# --XXXX--.net
KiCad netlist of a schematic drawn in EAGLE
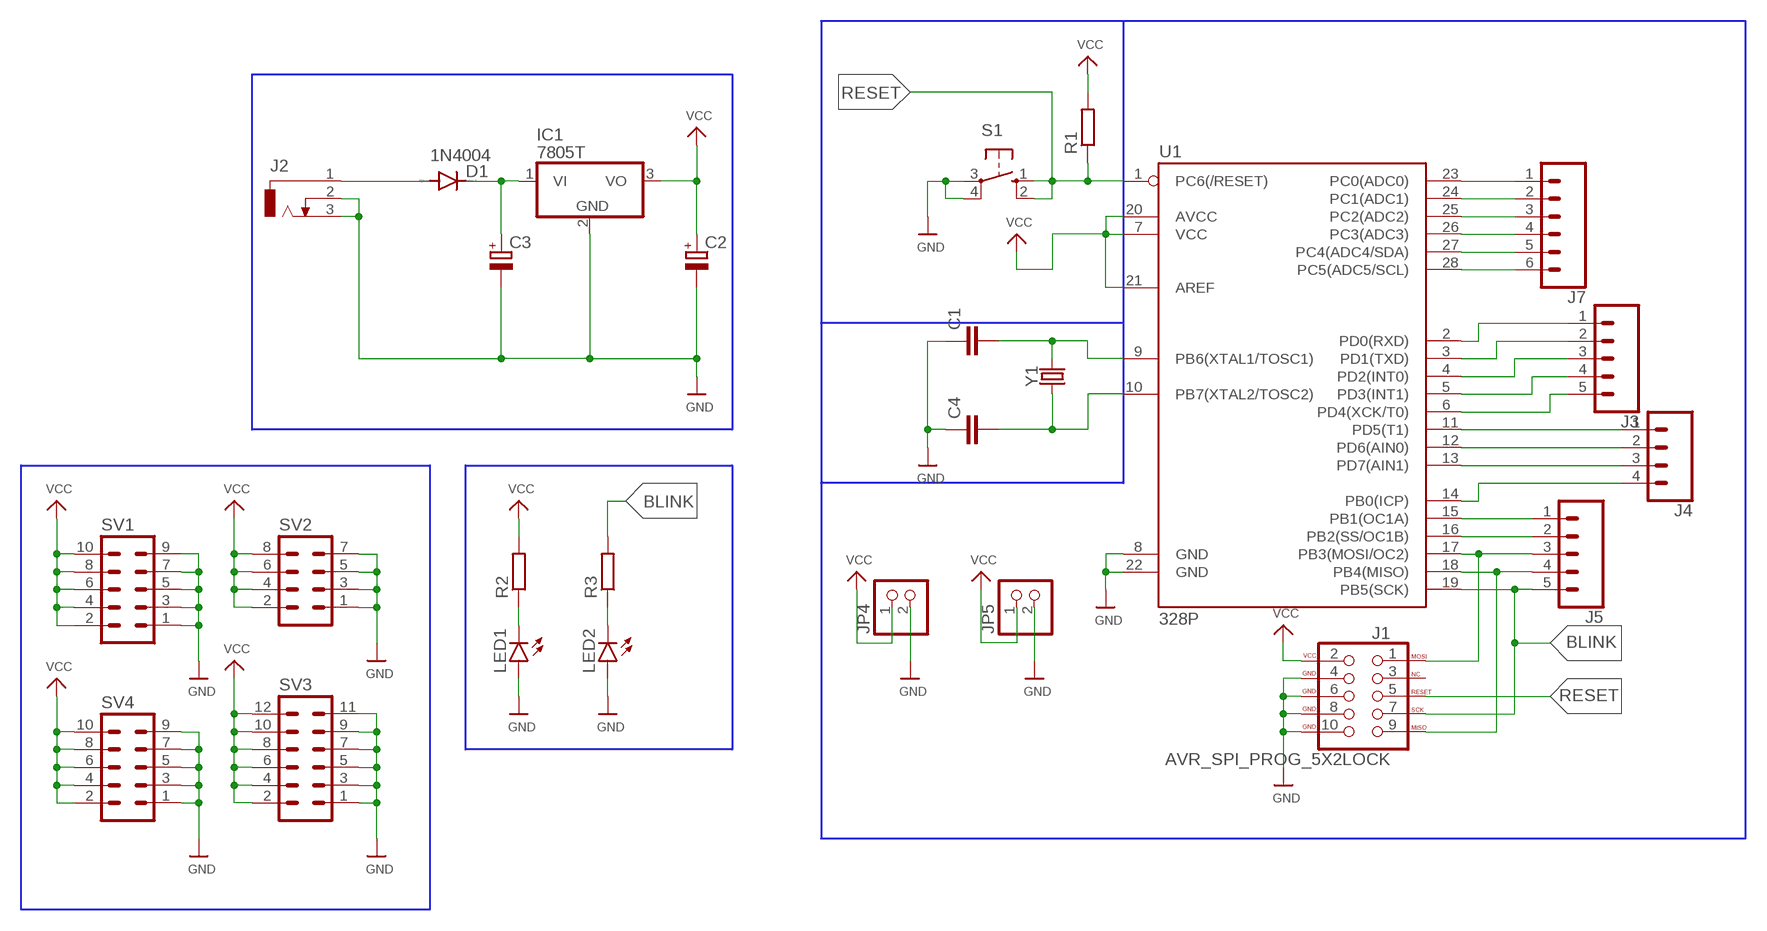
[diagram p0: schematic, sheet 1]

(export (version "E")
  (design (tool "Eeschema 10.0.6"))
  (components
    (comp (ref "C1")
      (value "C-EU050-024X044")
      (footprint "eagle-import:C050-024X044")
      (libsource (lib "eagle-import") (part "C-EU050-024X044"))
    )
    (comp (ref "C2")
      (value "CPOL-EUE2.5-5")
      (footprint "eagle-import:E2,5-5")
      (libsource (lib "eagle-import") (part "CPOL-EUE2.5-5"))
    )
    (comp (ref "C3")
      (value "CPOL-EUE2.5-7")
      (footprint "eagle-import:E2,5-7")
      (libsource (lib "eagle-import") (part "CPOL-EUE2.5-7"))
    )
    (comp (ref "C4")
      (value "C-EU050-024X044")
      (footprint "eagle-import:C050-024X044")
      (libsource (lib "eagle-import") (part "C-EU050-024X044"))
    )
    (comp (ref "D1")
      (value "1N4004")
      (footprint "eagle-import:DO41-10")
      (libsource (lib "eagle-import") (part "1N4004"))
    )
    (comp (ref "IC1")
      (value "7805T")
      (footprint "eagle-import:TO220H")
      (libsource (lib "eagle-import") (part "78T05"))
    )
    (comp (ref "J1")
      (value "AVR_SPI_PROG_5X2LOCK")
      (footprint "eagle-import:2X5-SHROUDED_LOCK")
      (libsource (lib "eagle-import") (part "AVR_SPI_PROG_5X2LOCK"))
    )
    (comp (ref "J2")
      (value "DCJ0303")
      (footprint "eagle-import:DCJ0303")
      (libsource (lib "eagle-import") (part "DCJ0303"))
    )
    (comp (ref "J3")
      (value "CONN_05")
      (footprint "eagle-import:1X05")
      (libsource (lib "eagle-import") (part "CONN_05"))
    )
    (comp (ref "J4")
      (value "CONN_04")
      (footprint "eagle-import:1X04")
      (libsource (lib "eagle-import") (part "CONN_04"))
    )
    (comp (ref "J5")
      (value "CONN_05")
      (footprint "eagle-import:1X05")
      (libsource (lib "eagle-import") (part "CONN_05"))
    )
    (comp (ref "J7")
      (value "CONN_06SILK_FEMALE_PTH")
      (footprint "eagle-import:1X06")
      (libsource (lib "eagle-import") (part "CONN_06SILK_FEMALE_PTH"))
    )
    (comp (ref "JP4")
      (value "PINHD-1X2")
      (footprint "eagle-import:1X02")
      (libsource (lib "eagle-import") (part "PINHD-1X2"))
    )
    (comp (ref "JP5")
      (value "PINHD-1X2")
      (footprint "eagle-import:1X02")
      (libsource (lib "eagle-import") (part "PINHD-1X2"))
    )
    (comp (ref "LED1")
      (value "LED3MM")
      (footprint "eagle-import:LED3MM")
      (libsource (lib "eagle-import") (part "LED3MM"))
    )
    (comp (ref "LED2")
      (value "LED3MM")
      (footprint "eagle-import:LED3MM")
      (libsource (lib "eagle-import") (part "LED3MM"))
    )
    (comp (ref "R1")
      (value "R-EU_0207/10")
      (footprint "eagle-import:0207_10")
      (libsource (lib "eagle-import") (part "R-EU_0207/10"))
    )
    (comp (ref "R2")
      (value "R-EU_0207/10")
      (footprint "eagle-import:0207_10")
      (libsource (lib "eagle-import") (part "R-EU_0207/10"))
    )
    (comp (ref "R3")
      (value "R-EU_0207/10")
      (footprint "eagle-import:0207_10")
      (libsource (lib "eagle-import") (part "R-EU_0207/10"))
    )
    (comp (ref "S1")
      (value "10-XX")
      (footprint "eagle-import:B3F-10XX")
      (fields (field (name "MPN") "B3F-1000"))
      (libsource (lib "eagle-import") (part "10-XX"))
    )
    (comp (ref "SV1")
      (value "MA05-2")
      (footprint "eagle-import:MA05-2")
      (libsource (lib "eagle-import") (part "MA05-2"))
    )
    (comp (ref "SV2")
      (value "MA04-2")
      (footprint "eagle-import:MA04-2")
      (libsource (lib "eagle-import") (part "MA04-2"))
    )
    (comp (ref "SV3")
      (value "MA06-2")
      (footprint "eagle-import:MA06-2")
      (libsource (lib "eagle-import") (part "MA06-2"))
    )
    (comp (ref "SV4")
      (value "MA05-2")
      (footprint "eagle-import:MA05-2")
      (libsource (lib "eagle-import") (part "MA05-2"))
    )
    (comp (ref "U1")
      (value "328P")
      (footprint "eagle-import:DIP28")
      (libsource (lib "eagle-import") (part "ATMEGA328P_PDIP"))
    )
    (comp (ref "Y1")
      (value "CRYSTALPTH-HC49UV")
      (footprint "eagle-import:HC49U")
      (libsource (lib "eagle-import") (part "CRYSTALPTH-HC49UV"))
    )
  )
  (nets
    (net (code "1") (name "/BLINK") (class "Default")
      (node (ref "J1") (pin "7") (pinfunction "SCK_7") (pintype "passive"))
      (node (ref "J5") (pin "5") (pinfunction "5_5") (pintype "passive"))
      (node (ref "R3") (pin "2") (pinfunction "2_2") (pintype "passive"))
      (node (ref "U1") (pin "19") (pinfunction "PB5(SCK)_19") (pintype "bidirectional"))
    )
    (net (code "2") (name "/RESET") (class "Default")
      (node (ref "J1") (pin "5") (pinfunction "RESET_5") (pintype "passive"))
      (node (ref "R1") (pin "1") (pinfunction "1_1") (pintype "passive"))
      (node (ref "S1") (pin "1") (pinfunction "S_1") (pintype "passive"))
      (node (ref "S1") (pin "2") (pinfunction "S1_2") (pintype "passive"))
      (node (ref "U1") (pin "1") (pinfunction "PC6(/RESET)_1") (pintype "bidirectional"))
    )
    (net (code "3") (name "GND") (class "Default")
      (node (ref "C1") (pin "1") (pinfunction "1_1") (pintype "passive"))
      (node (ref "C2") (pin "-") (pinfunction "-_-") (pintype "passive"))
      (node (ref "C3") (pin "-") (pinfunction "-_-") (pintype "passive"))
      (node (ref "C4") (pin "1") (pinfunction "1_1") (pintype "passive"))
      (node (ref "IC1") (pin "2") (pinfunction "GND_2") (pintype "passive"))
      (node (ref "J1") (pin "10") (pinfunction "GND_10") (pintype "power_in"))
      (node (ref "J1") (pin "4") (pinfunction "GND_4") (pintype "power_in"))
      (node (ref "J1") (pin "6") (pinfunction "GND_6") (pintype "power_in"))
      (node (ref "J1") (pin "8") (pinfunction "GND_8") (pintype "power_in"))
      (node (ref "J2") (pin "2") (pinfunction "2_2") (pintype "passive"))
      (node (ref "J2") (pin "3") (pinfunction "3_3") (pintype "passive"))
      (node (ref "JP4") (pin "2") (pinfunction "2_2") (pintype "passive"))
      (node (ref "JP5") (pin "2") (pinfunction "2_2") (pintype "passive"))
      (node (ref "LED1") (pin "A") (pinfunction "A_A") (pintype "passive"))
      (node (ref "LED2") (pin "A") (pinfunction "A_A") (pintype "passive"))
      (node (ref "S1") (pin "3") (pinfunction "P_3") (pintype "passive"))
      (node (ref "S1") (pin "4") (pinfunction "P1_4") (pintype "passive"))
      (node (ref "SV1") (pin "1") (pinfunction "1_1") (pintype "passive"))
      (node (ref "SV1") (pin "3") (pinfunction "3_3") (pintype "passive"))
      (node (ref "SV1") (pin "5") (pinfunction "5_5") (pintype "passive"))
      (node (ref "SV1") (pin "7") (pinfunction "7_7") (pintype "passive"))
      (node (ref "SV1") (pin "9") (pinfunction "9_9") (pintype "passive"))
      (node (ref "SV2") (pin "1") (pinfunction "1_1") (pintype "passive"))
      (node (ref "SV2") (pin "3") (pinfunction "3_3") (pintype "passive"))
      (node (ref "SV2") (pin "5") (pinfunction "5_5") (pintype "passive"))
      (node (ref "SV2") (pin "7") (pinfunction "7_7") (pintype "passive"))
      (node (ref "SV3") (pin "1") (pinfunction "1_1") (pintype "passive"))
      (node (ref "SV3") (pin "11") (pinfunction "11_11") (pintype "passive"))
      (node (ref "SV3") (pin "3") (pinfunction "3_3") (pintype "passive"))
      (node (ref "SV3") (pin "5") (pinfunction "5_5") (pintype "passive"))
      (node (ref "SV3") (pin "7") (pinfunction "7_7") (pintype "passive"))
      (node (ref "SV3") (pin "9") (pinfunction "9_9") (pintype "passive"))
      (node (ref "SV4") (pin "1") (pinfunction "1_1") (pintype "passive"))
      (node (ref "SV4") (pin "3") (pinfunction "3_3") (pintype "passive"))
      (node (ref "SV4") (pin "5") (pinfunction "5_5") (pintype "passive"))
      (node (ref "SV4") (pin "7") (pinfunction "7_7") (pintype "passive"))
      (node (ref "SV4") (pin "9") (pinfunction "9_9") (pintype "passive"))
      (node (ref "U1") (pin "22") (pinfunction "GND_22") (pintype "bidirectional"))
      (node (ref "U1") (pin "8") (pinfunction "GND_8") (pintype "bidirectional"))
    )
    (net (code "4") (name "Net-(D1-PadA)") (class "Default")
      (node (ref "D1") (pin "A") (pinfunction "A_A") (pintype "passive"))
      (node (ref "J2") (pin "1") (pinfunction "1_1") (pintype "passive"))
    )
    (net (code "5") (name "Net-(IC1-VI)") (class "Default")
      (node (ref "C3") (pin "+") (pinfunction "+_+") (pintype "passive"))
      (node (ref "D1") (pin "C") (pinfunction "C_C") (pintype "passive"))
      (node (ref "IC1") (pin "1") (pinfunction "VI_1") (pintype "input"))
    )
    (net (code "6") (name "Net-(J1-MISO)") (class "Default")
      (node (ref "J1") (pin "9") (pinfunction "MISO_9") (pintype "passive"))
      (node (ref "J5") (pin "4") (pinfunction "4_4") (pintype "passive"))
      (node (ref "U1") (pin "18") (pinfunction "PB4(MISO)_18") (pintype "bidirectional"))
    )
    (net (code "7") (name "Net-(J1-MOSI)") (class "Default")
      (node (ref "J1") (pin "1") (pinfunction "MOSI_1") (pintype "passive"))
      (node (ref "J5") (pin "3") (pinfunction "3_3") (pintype "passive"))
      (node (ref "U1") (pin "17") (pinfunction "PB3(MOSI/OC2)_17") (pintype "bidirectional"))
    )
    (net (code "8") (name "Net-(LED1-C)") (class "Default")
      (node (ref "LED1") (pin "K") (pinfunction "C_K") (pintype "passive"))
      (node (ref "R2") (pin "1") (pinfunction "1_1") (pintype "passive"))
    )
    (net (code "9") (name "Net-(LED2-C)") (class "Default")
      (node (ref "LED2") (pin "K") (pinfunction "C_K") (pintype "passive"))
      (node (ref "R3") (pin "1") (pinfunction "1_1") (pintype "passive"))
    )
    (net (code "10") (name "Net-(U1-PB0(ICP))") (class "Default")
      (node (ref "J4") (pin "4") (pinfunction "4_4") (pintype "passive"))
      (node (ref "U1") (pin "14") (pinfunction "PB0(ICP)_14") (pintype "bidirectional"))
    )
    (net (code "11") (name "Net-(U1-PB1(OC1A))") (class "Default")
      (node (ref "J5") (pin "1") (pinfunction "1_1") (pintype "passive"))
      (node (ref "U1") (pin "15") (pinfunction "PB1(OC1A)_15") (pintype "bidirectional"))
    )
    (net (code "12") (name "Net-(U1-PB2(SS{slash}OC1B))") (class "Default")
      (node (ref "J5") (pin "2") (pinfunction "2_2") (pintype "passive"))
      (node (ref "U1") (pin "16") (pinfunction "PB2(SS/OC1B)_16") (pintype "bidirectional"))
    )
    (net (code "13") (name "Net-(U1-PB6(XTAL1{slash}TOSC1))") (class "Default")
      (node (ref "C1") (pin "2") (pinfunction "2_2") (pintype "passive"))
      (node (ref "U1") (pin "9") (pinfunction "PB6(XTAL1/TOSC1)_9") (pintype "bidirectional"))
      (node (ref "Y1") (pin "2") (pinfunction "2_2") (pintype "passive"))
    )
    (net (code "14") (name "Net-(U1-PB7(XTAL2{slash}TOSC2))") (class "Default")
      (node (ref "C4") (pin "2") (pinfunction "2_2") (pintype "passive"))
      (node (ref "U1") (pin "10") (pinfunction "PB7(XTAL2/TOSC2)_10") (pintype "bidirectional"))
      (node (ref "Y1") (pin "1") (pinfunction "1_1") (pintype "passive"))
    )
    (net (code "15") (name "Net-(U1-PC0(ADC0))") (class "Default")
      (node (ref "J7") (pin "1") (pinfunction "1_1") (pintype "passive"))
      (node (ref "U1") (pin "23") (pinfunction "PC0(ADC0)_23") (pintype "bidirectional"))
    )
    (net (code "16") (name "Net-(U1-PC1(ADC1))") (class "Default")
      (node (ref "J7") (pin "2") (pinfunction "2_2") (pintype "passive"))
      (node (ref "U1") (pin "24") (pinfunction "PC1(ADC1)_24") (pintype "bidirectional"))
    )
    (net (code "17") (name "Net-(U1-PC2(ADC2))") (class "Default")
      (node (ref "J7") (pin "3") (pinfunction "3_3") (pintype "passive"))
      (node (ref "U1") (pin "25") (pinfunction "PC2(ADC2)_25") (pintype "bidirectional"))
    )
    (net (code "18") (name "Net-(U1-PC3(ADC3))") (class "Default")
      (node (ref "J7") (pin "4") (pinfunction "4_4") (pintype "passive"))
      (node (ref "U1") (pin "26") (pinfunction "PC3(ADC3)_26") (pintype "bidirectional"))
    )
    (net (code "19") (name "Net-(U1-PC4(ADC4{slash}SDA))") (class "Default")
      (node (ref "J7") (pin "5") (pinfunction "5_5") (pintype "passive"))
      (node (ref "U1") (pin "27") (pinfunction "PC4(ADC4/SDA)_27") (pintype "bidirectional"))
    )
    (net (code "20") (name "Net-(U1-PC5(ADC5{slash}SCL))") (class "Default")
      (node (ref "J7") (pin "6") (pinfunction "6_6") (pintype "passive"))
      (node (ref "U1") (pin "28") (pinfunction "PC5(ADC5/SCL)_28") (pintype "bidirectional"))
    )
    (net (code "21") (name "Net-(U1-PD0(RXD))") (class "Default")
      (node (ref "J3") (pin "1") (pinfunction "1_1") (pintype "passive"))
      (node (ref "U1") (pin "2") (pinfunction "PD0(RXD)_2") (pintype "bidirectional"))
    )
    (net (code "22") (name "Net-(U1-PD1(TXD))") (class "Default")
      (node (ref "J3") (pin "2") (pinfunction "2_2") (pintype "passive"))
      (node (ref "U1") (pin "3") (pinfunction "PD1(TXD)_3") (pintype "bidirectional"))
    )
    (net (code "23") (name "Net-(U1-PD2(INT0))") (class "Default")
      (node (ref "J3") (pin "3") (pinfunction "3_3") (pintype "passive"))
      (node (ref "U1") (pin "4") (pinfunction "PD2(INT0)_4") (pintype "bidirectional"))
    )
    (net (code "24") (name "Net-(U1-PD3(INT1))") (class "Default")
      (node (ref "J3") (pin "4") (pinfunction "4_4") (pintype "passive"))
      (node (ref "U1") (pin "5") (pinfunction "PD3(INT1)_5") (pintype "bidirectional"))
    )
    (net (code "25") (name "Net-(U1-PD4(XCK{slash}T0))") (class "Default")
      (node (ref "J3") (pin "5") (pinfunction "5_5") (pintype "passive"))
      (node (ref "U1") (pin "6") (pinfunction "PD4(XCK/T0)_6") (pintype "bidirectional"))
    )
    (net (code "26") (name "Net-(U1-PD5(T1))") (class "Default")
      (node (ref "J4") (pin "1") (pinfunction "1_1") (pintype "passive"))
      (node (ref "U1") (pin "11") (pinfunction "PD5(T1)_11") (pintype "bidirectional"))
    )
    (net (code "27") (name "Net-(U1-PD6(AIN0))") (class "Default")
      (node (ref "J4") (pin "2") (pinfunction "2_2") (pintype "passive"))
      (node (ref "U1") (pin "12") (pinfunction "PD6(AIN0)_12") (pintype "bidirectional"))
    )
    (net (code "28") (name "Net-(U1-PD7(AIN1))") (class "Default")
      (node (ref "J4") (pin "3") (pinfunction "3_3") (pintype "passive"))
      (node (ref "U1") (pin "13") (pinfunction "PD7(AIN1)_13") (pintype "bidirectional"))
    )
    (net (code "29") (name "VCC") (class "Default")
      (node (ref "C2") (pin "+") (pinfunction "+_+") (pintype "passive"))
      (node (ref "IC1") (pin "3") (pinfunction "VO_3") (pintype "passive"))
      (node (ref "J1") (pin "2") (pinfunction "VCC_2") (pintype "power_in"))
      (node (ref "JP4") (pin "1") (pinfunction "1_1") (pintype "passive"))
      (node (ref "JP5") (pin "1") (pinfunction "1_1") (pintype "passive"))
      (node (ref "R1") (pin "2") (pinfunction "2_2") (pintype "passive"))
      (node (ref "R2") (pin "2") (pinfunction "2_2") (pintype "passive"))
      (node (ref "SV1") (pin "10") (pinfunction "10_10") (pintype "passive"))
      (node (ref "SV1") (pin "2") (pinfunction "2_2") (pintype "passive"))
      (node (ref "SV1") (pin "4") (pinfunction "4_4") (pintype "passive"))
      (node (ref "SV1") (pin "6") (pinfunction "6_6") (pintype "passive"))
      (node (ref "SV1") (pin "8") (pinfunction "8_8") (pintype "passive"))
      (node (ref "SV2") (pin "2") (pinfunction "2_2") (pintype "passive"))
      (node (ref "SV2") (pin "4") (pinfunction "4_4") (pintype "passive"))
      (node (ref "SV2") (pin "6") (pinfunction "6_6") (pintype "passive"))
      (node (ref "SV2") (pin "8") (pinfunction "8_8") (pintype "passive"))
      (node (ref "SV3") (pin "10") (pinfunction "10_10") (pintype "passive"))
      (node (ref "SV3") (pin "12") (pinfunction "12_12") (pintype "passive"))
      (node (ref "SV3") (pin "2") (pinfunction "2_2") (pintype "passive"))
      (node (ref "SV3") (pin "4") (pinfunction "4_4") (pintype "passive"))
      (node (ref "SV3") (pin "6") (pinfunction "6_6") (pintype "passive"))
      (node (ref "SV3") (pin "8") (pinfunction "8_8") (pintype "passive"))
      (node (ref "SV4") (pin "10") (pinfunction "10_10") (pintype "passive"))
      (node (ref "SV4") (pin "2") (pinfunction "2_2") (pintype "passive"))
      (node (ref "SV4") (pin "4") (pinfunction "4_4") (pintype "passive"))
      (node (ref "SV4") (pin "6") (pinfunction "6_6") (pintype "passive"))
      (node (ref "SV4") (pin "8") (pinfunction "8_8") (pintype "passive"))
      (node (ref "U1") (pin "20") (pinfunction "AVCC_20") (pintype "bidirectional"))
      (node (ref "U1") (pin "21") (pinfunction "AREF_21") (pintype "bidirectional"))
      (node (ref "U1") (pin "7") (pinfunction "VCC_7") (pintype "bidirectional"))
    )
    (net (code "30") (name "unconnected-(J1-NC-Pad3)") (class "Default")
      (node (ref "J1") (pin "3") (pinfunction "NC_3") (pintype "no_connect"))
    )
  )
)
